# v2_0_-_Calibra_o.net
KiCad netlist of a schematic drawn in EAGLE
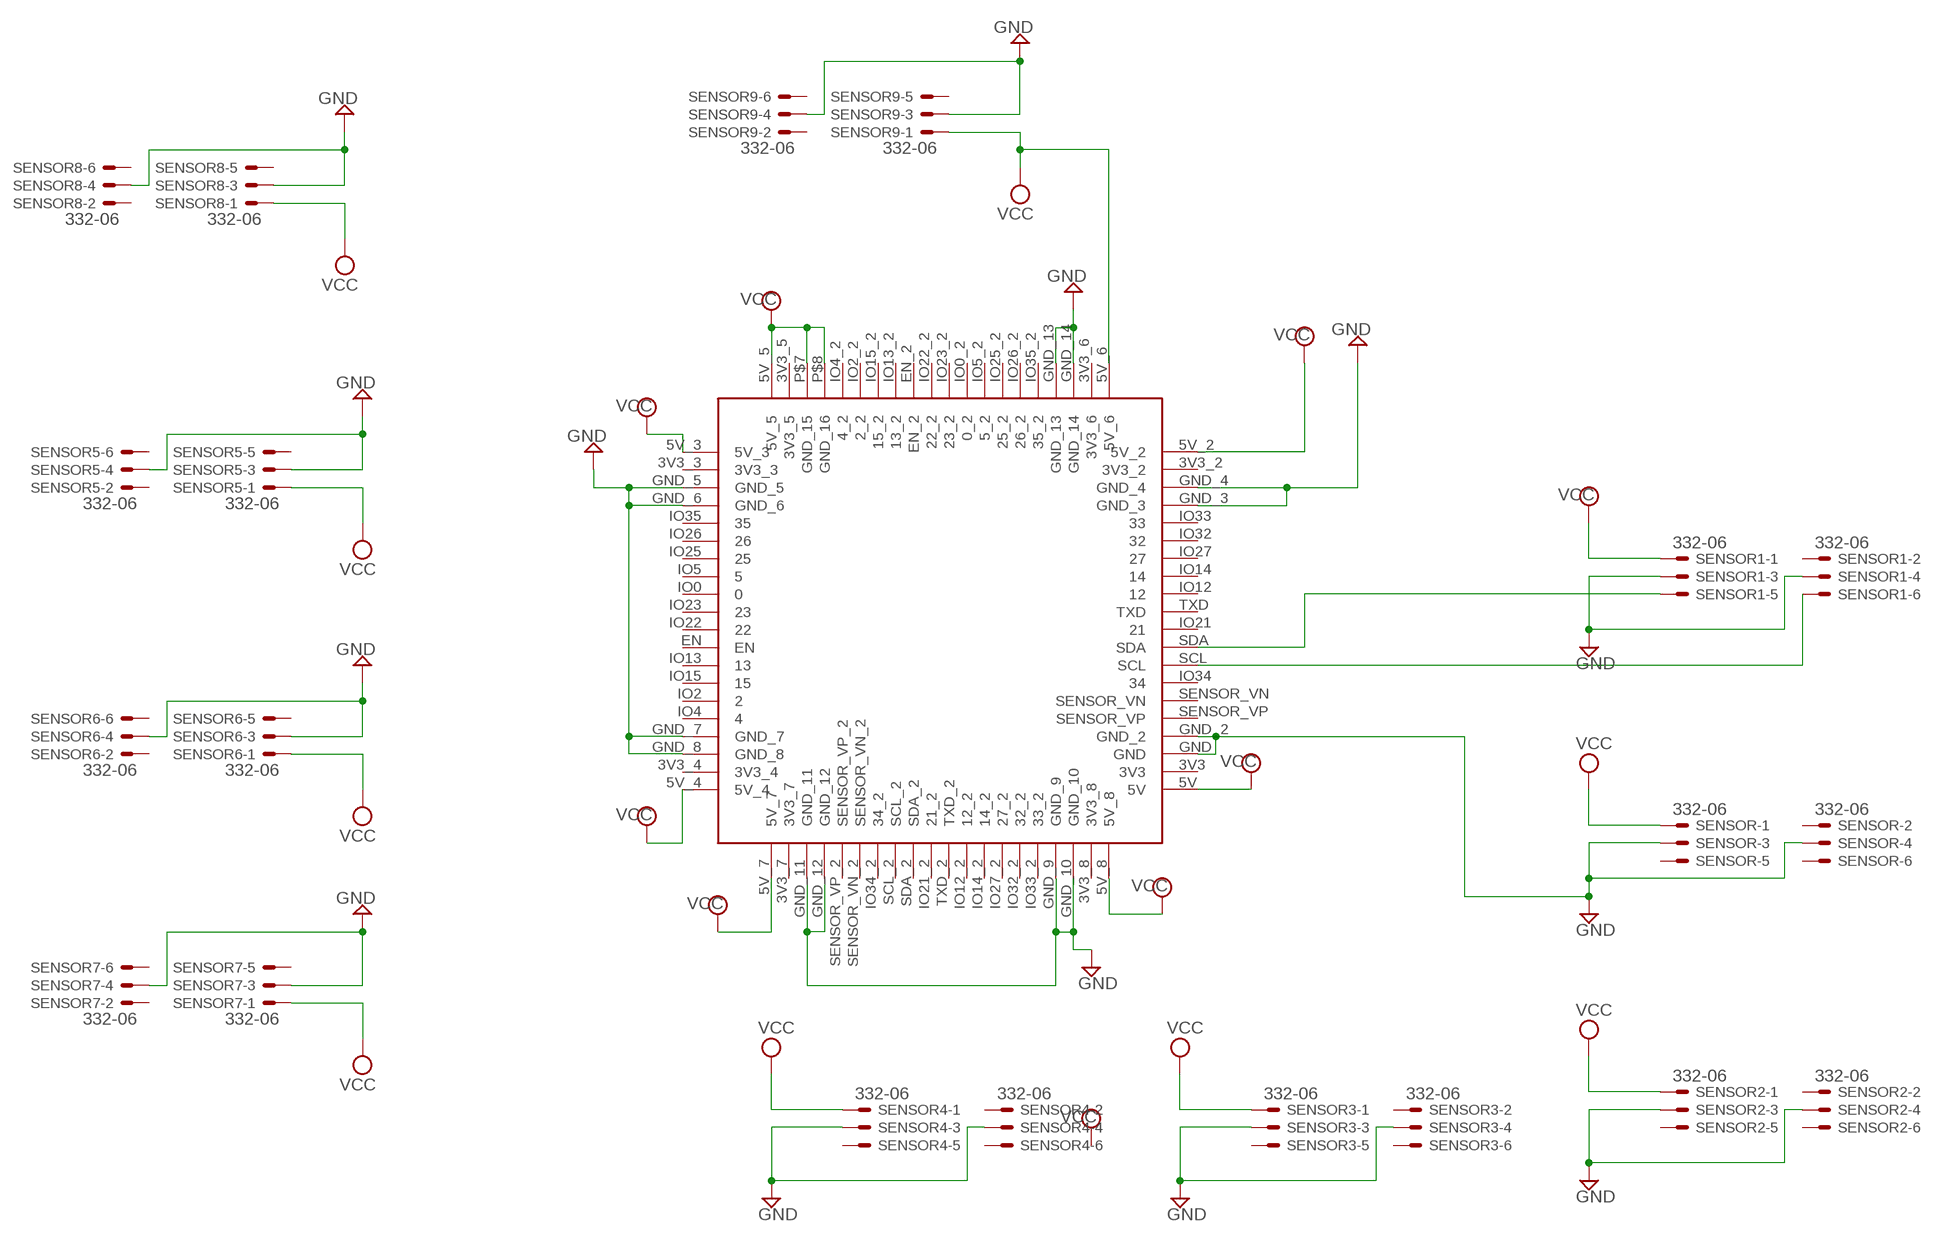
[diagram p0: schematic, sheet 1]

(export (version "E")
  (design (tool "Eeschema 10.0.6"))
  (components
    (comp (ref "SENSOR")
      (value "332-06")
      (footprint "eagle-import:332-06")
      (libsource (lib "eagle-import") (part "332-06"))
    )
    (comp (ref "SENSOR1")
      (value "332-06")
      (footprint "eagle-import:332-06")
      (libsource (lib "eagle-import") (part "332-06"))
    )
    (comp (ref "SENSOR2")
      (value "332-06")
      (footprint "eagle-import:332-06")
      (libsource (lib "eagle-import") (part "332-06"))
    )
    (comp (ref "SENSOR3")
      (value "332-06")
      (footprint "eagle-import:332-06")
      (libsource (lib "eagle-import") (part "332-06"))
    )
    (comp (ref "SENSOR4")
      (value "332-06")
      (footprint "eagle-import:332-06")
      (libsource (lib "eagle-import") (part "332-06"))
    )
    (comp (ref "SENSOR5")
      (value "332-06")
      (footprint "eagle-import:332-06")
      (libsource (lib "eagle-import") (part "332-06"))
    )
    (comp (ref "SENSOR6")
      (value "332-06")
      (footprint "eagle-import:332-06")
      (libsource (lib "eagle-import") (part "332-06"))
    )
    (comp (ref "SENSOR7")
      (value "332-06")
      (footprint "eagle-import:332-06")
      (libsource (lib "eagle-import") (part "332-06"))
    )
    (comp (ref "SENSOR8")
      (value "332-06")
      (footprint "eagle-import:332-06")
      (libsource (lib "eagle-import") (part "332-06"))
    )
    (comp (ref "SENSOR9")
      (value "332-06")
      (footprint "eagle-import:332-06")
      (libsource (lib "eagle-import") (part "332-06"))
    )
    (comp (ref "U$1")
      (value "WT32_SC01")
      (footprint "eagle-import:WT32")
      (libsource (lib "eagle-import") (part "WT32_SC01"))
    )
  )
  (nets
    (net (code "1") (name "GND") (class "Default")
      (node (ref "SENSOR") (pin "3") (pinfunction "S_3") (pintype "passive"))
      (node (ref "SENSOR") (pin "4") (pinfunction "S_4") (pintype "passive"))
      (node (ref "SENSOR1") (pin "3") (pinfunction "S_3") (pintype "passive"))
      (node (ref "SENSOR1") (pin "4") (pinfunction "S_4") (pintype "passive"))
      (node (ref "SENSOR2") (pin "3") (pinfunction "S_3") (pintype "passive"))
      (node (ref "SENSOR2") (pin "4") (pinfunction "S_4") (pintype "passive"))
      (node (ref "SENSOR3") (pin "3") (pinfunction "S_3") (pintype "passive"))
      (node (ref "SENSOR3") (pin "4") (pinfunction "S_4") (pintype "passive"))
      (node (ref "SENSOR4") (pin "3") (pinfunction "S_3") (pintype "passive"))
      (node (ref "SENSOR4") (pin "4") (pinfunction "S_4") (pintype "passive"))
      (node (ref "SENSOR5") (pin "3") (pinfunction "S_3") (pintype "passive"))
      (node (ref "SENSOR5") (pin "4") (pinfunction "S_4") (pintype "passive"))
      (node (ref "SENSOR6") (pin "3") (pinfunction "S_3") (pintype "passive"))
      (node (ref "SENSOR6") (pin "4") (pinfunction "S_4") (pintype "passive"))
      (node (ref "SENSOR7") (pin "3") (pinfunction "S_3") (pintype "passive"))
      (node (ref "SENSOR7") (pin "4") (pinfunction "S_4") (pintype "passive"))
      (node (ref "SENSOR8") (pin "3") (pinfunction "S_3") (pintype "passive"))
      (node (ref "SENSOR8") (pin "4") (pinfunction "S_4") (pintype "passive"))
      (node (ref "SENSOR9") (pin "3") (pinfunction "S_3") (pintype "passive"))
      (node (ref "SENSOR9") (pin "4") (pinfunction "S_4") (pintype "passive"))
      (node (ref "U$1") (pin "GND") (pinfunction "GND_GND") (pintype "bidirectional"))
      (node (ref "U$1") (pin "GND_10") (pinfunction "GND_10_GND_10") (pintype "bidirectional"))
      (node (ref "U$1") (pin "GND_11") (pinfunction "GND_11_GND_11") (pintype "bidirectional"))
      (node (ref "U$1") (pin "GND_12") (pinfunction "GND_12_GND_12") (pintype "bidirectional"))
      (node (ref "U$1") (pin "GND_13") (pinfunction "GND_13_GND_13") (pintype "bidirectional"))
      (node (ref "U$1") (pin "GND_14") (pinfunction "GND_14_GND_14") (pintype "bidirectional"))
      (node (ref "U$1") (pin "GND_2") (pinfunction "GND_2_GND_2") (pintype "bidirectional"))
      (node (ref "U$1") (pin "GND_3") (pinfunction "GND_3_GND_3") (pintype "bidirectional"))
      (node (ref "U$1") (pin "GND_4") (pinfunction "GND_4_GND_4") (pintype "bidirectional"))
      (node (ref "U$1") (pin "GND_5") (pinfunction "GND_5_GND_5") (pintype "bidirectional"))
      (node (ref "U$1") (pin "GND_6") (pinfunction "GND_6_GND_6") (pintype "bidirectional"))
      (node (ref "U$1") (pin "GND_7") (pinfunction "GND_7_GND_7") (pintype "bidirectional"))
      (node (ref "U$1") (pin "GND_8") (pinfunction "GND_8_GND_8") (pintype "bidirectional"))
      (node (ref "U$1") (pin "GND_9") (pinfunction "GND_9_GND_9") (pintype "bidirectional"))
    )
    (net (code "2") (name "Net-(SENSOR1E-S)") (class "Default")
      (node (ref "SENSOR1") (pin "5") (pinfunction "S_5") (pintype "passive"))
      (node (ref "U$1") (pin "SDA") (pinfunction "SDA_SDA") (pintype "bidirectional"))
    )
    (net (code "3") (name "Net-(SENSOR1F-S)") (class "Default")
      (node (ref "SENSOR1") (pin "6") (pinfunction "S_6") (pintype "passive"))
      (node (ref "U$1") (pin "SCL") (pinfunction "SCL_SCL") (pintype "bidirectional"))
    )
    (net (code "4") (name "VCC") (class "Default")
      (node (ref "SENSOR") (pin "1") (pinfunction "S_1") (pintype "passive"))
      (node (ref "SENSOR1") (pin "1") (pinfunction "S_1") (pintype "passive"))
      (node (ref "SENSOR2") (pin "1") (pinfunction "S_1") (pintype "passive"))
      (node (ref "SENSOR3") (pin "1") (pinfunction "S_1") (pintype "passive"))
      (node (ref "SENSOR4") (pin "1") (pinfunction "S_1") (pintype "passive"))
      (node (ref "SENSOR5") (pin "1") (pinfunction "S_1") (pintype "passive"))
      (node (ref "SENSOR6") (pin "1") (pinfunction "S_1") (pintype "passive"))
      (node (ref "SENSOR7") (pin "1") (pinfunction "S_1") (pintype "passive"))
      (node (ref "SENSOR8") (pin "1") (pinfunction "S_1") (pintype "passive"))
      (node (ref "SENSOR9") (pin "1") (pinfunction "S_1") (pintype "passive"))
      (node (ref "U$1") (pin "5V") (pinfunction "5V_5V") (pintype "bidirectional"))
      (node (ref "U$1") (pin "5V_2") (pinfunction "5V_2_5V_2") (pintype "bidirectional"))
      (node (ref "U$1") (pin "5V_3") (pinfunction "5V_3_5V_3") (pintype "bidirectional"))
      (node (ref "U$1") (pin "5V_4") (pinfunction "5V_4_5V_4") (pintype "bidirectional"))
      (node (ref "U$1") (pin "5V_5") (pinfunction "5V_5_5V_5") (pintype "bidirectional"))
      (node (ref "U$1") (pin "5V_6") (pinfunction "5V_6_5V_6") (pintype "bidirectional"))
      (node (ref "U$1") (pin "5V_7") (pinfunction "5V_7_5V_7") (pintype "bidirectional"))
      (node (ref "U$1") (pin "5V_8") (pinfunction "5V_8_5V_8") (pintype "bidirectional"))
      (node (ref "U$1") (pin "P$7") (pinfunction "GND_15_P$7") (pintype "bidirectional"))
      (node (ref "U$1") (pin "P$8") (pinfunction "GND_16_P$8") (pintype "bidirectional"))
    )
    (net (code "5") (name "unconnected-(SENSOR1B-S-Pad2)") (class "Default")
      (node (ref "SENSOR1") (pin "2") (pinfunction "S_2") (pintype "passive"))
    )
    (net (code "6") (name "unconnected-(SENSOR2B-S-Pad2)") (class "Default")
      (node (ref "SENSOR2") (pin "2") (pinfunction "S_2") (pintype "passive"))
    )
    (net (code "7") (name "unconnected-(SENSOR2E-S-Pad5)") (class "Default")
      (node (ref "SENSOR2") (pin "5") (pinfunction "S_5") (pintype "passive"))
    )
    (net (code "8") (name "unconnected-(SENSOR2F-S-Pad6)") (class "Default")
      (node (ref "SENSOR2") (pin "6") (pinfunction "S_6") (pintype "passive"))
    )
    (net (code "9") (name "unconnected-(SENSOR3B-S-Pad2)") (class "Default")
      (node (ref "SENSOR3") (pin "2") (pinfunction "S_2") (pintype "passive"))
    )
    (net (code "10") (name "unconnected-(SENSOR3E-S-Pad5)") (class "Default")
      (node (ref "SENSOR3") (pin "5") (pinfunction "S_5") (pintype "passive"))
    )
    (net (code "11") (name "unconnected-(SENSOR3F-S-Pad6)") (class "Default")
      (node (ref "SENSOR3") (pin "6") (pinfunction "S_6") (pintype "passive"))
    )
    (net (code "12") (name "unconnected-(SENSOR4B-S-Pad2)") (class "Default")
      (node (ref "SENSOR4") (pin "2") (pinfunction "S_2") (pintype "passive"))
    )
    (net (code "13") (name "unconnected-(SENSOR4E-S-Pad5)") (class "Default")
      (node (ref "SENSOR4") (pin "5") (pinfunction "S_5") (pintype "passive"))
    )
    (net (code "14") (name "unconnected-(SENSOR4F-S-Pad6)") (class "Default")
      (node (ref "SENSOR4") (pin "6") (pinfunction "S_6") (pintype "passive"))
    )
    (net (code "15") (name "unconnected-(SENSOR5B-S-Pad2)") (class "Default")
      (node (ref "SENSOR5") (pin "2") (pinfunction "S_2") (pintype "passive"))
    )
    (net (code "16") (name "unconnected-(SENSOR5E-S-Pad5)") (class "Default")
      (node (ref "SENSOR5") (pin "5") (pinfunction "S_5") (pintype "passive"))
    )
    (net (code "17") (name "unconnected-(SENSOR5F-S-Pad6)") (class "Default")
      (node (ref "SENSOR5") (pin "6") (pinfunction "S_6") (pintype "passive"))
    )
    (net (code "18") (name "unconnected-(SENSOR6B-S-Pad2)") (class "Default")
      (node (ref "SENSOR6") (pin "2") (pinfunction "S_2") (pintype "passive"))
    )
    (net (code "19") (name "unconnected-(SENSOR6E-S-Pad5)") (class "Default")
      (node (ref "SENSOR6") (pin "5") (pinfunction "S_5") (pintype "passive"))
    )
    (net (code "20") (name "unconnected-(SENSOR6F-S-Pad6)") (class "Default")
      (node (ref "SENSOR6") (pin "6") (pinfunction "S_6") (pintype "passive"))
    )
    (net (code "21") (name "unconnected-(SENSOR7B-S-Pad2)") (class "Default")
      (node (ref "SENSOR7") (pin "2") (pinfunction "S_2") (pintype "passive"))
    )
    (net (code "22") (name "unconnected-(SENSOR7E-S-Pad5)") (class "Default")
      (node (ref "SENSOR7") (pin "5") (pinfunction "S_5") (pintype "passive"))
    )
    (net (code "23") (name "unconnected-(SENSOR7F-S-Pad6)") (class "Default")
      (node (ref "SENSOR7") (pin "6") (pinfunction "S_6") (pintype "passive"))
    )
    (net (code "24") (name "unconnected-(SENSOR8B-S-Pad2)") (class "Default")
      (node (ref "SENSOR8") (pin "2") (pinfunction "S_2") (pintype "passive"))
    )
    (net (code "25") (name "unconnected-(SENSOR8E-S-Pad5)") (class "Default")
      (node (ref "SENSOR8") (pin "5") (pinfunction "S_5") (pintype "passive"))
    )
    (net (code "26") (name "unconnected-(SENSOR8F-S-Pad6)") (class "Default")
      (node (ref "SENSOR8") (pin "6") (pinfunction "S_6") (pintype "passive"))
    )
    (net (code "27") (name "unconnected-(SENSOR9B-S-Pad2)") (class "Default")
      (node (ref "SENSOR9") (pin "2") (pinfunction "S_2") (pintype "passive"))
    )
    (net (code "28") (name "unconnected-(SENSOR9E-S-Pad5)") (class "Default")
      (node (ref "SENSOR9") (pin "5") (pinfunction "S_5") (pintype "passive"))
    )
    (net (code "29") (name "unconnected-(SENSOR9F-S-Pad6)") (class "Default")
      (node (ref "SENSOR9") (pin "6") (pinfunction "S_6") (pintype "passive"))
    )
    (net (code "30") (name "unconnected-(SENSORB-S-Pad2)") (class "Default")
      (node (ref "SENSOR") (pin "2") (pinfunction "S_2") (pintype "passive"))
    )
    (net (code "31") (name "unconnected-(SENSORE-S-Pad5)") (class "Default")
      (node (ref "SENSOR") (pin "5") (pinfunction "S_5") (pintype "passive"))
    )
    (net (code "32") (name "unconnected-(SENSORF-S-Pad6)") (class "Default")
      (node (ref "SENSOR") (pin "6") (pinfunction "S_6") (pintype "passive"))
    )
    (net (code "33") (name "unconnected-(U$1-0-PadIO0)") (class "Default")
      (node (ref "U$1") (pin "IO0") (pinfunction "0_IO0") (pintype "bidirectional"))
    )
    (net (code "34") (name "unconnected-(U$1-0_2-PadIO0_2)") (class "Default")
      (node (ref "U$1") (pin "IO0_2") (pinfunction "0_2_IO0_2") (pintype "bidirectional"))
    )
    (net (code "35") (name "unconnected-(U$1-2-PadIO2)") (class "Default")
      (node (ref "U$1") (pin "IO2") (pinfunction "2_IO2") (pintype "bidirectional"))
    )
    (net (code "36") (name "unconnected-(U$1-2_2-PadIO2_2)") (class "Default")
      (node (ref "U$1") (pin "IO2_2") (pinfunction "2_2_IO2_2") (pintype "bidirectional"))
    )
    (net (code "37") (name "unconnected-(U$1-4-PadIO4)") (class "Default")
      (node (ref "U$1") (pin "IO4") (pinfunction "4_IO4") (pintype "bidirectional"))
    )
    (net (code "38") (name "unconnected-(U$1-4_2-PadIO4_2)") (class "Default")
      (node (ref "U$1") (pin "IO4_2") (pinfunction "4_2_IO4_2") (pintype "bidirectional"))
    )
    (net (code "39") (name "unconnected-(U$1-5-PadIO5)") (class "Default")
      (node (ref "U$1") (pin "IO5") (pinfunction "5_IO5") (pintype "bidirectional"))
    )
    (net (code "40") (name "unconnected-(U$1-5_2-PadIO5_2)") (class "Default")
      (node (ref "U$1") (pin "IO5_2") (pinfunction "5_2_IO5_2") (pintype "bidirectional"))
    )
    (net (code "41") (name "unconnected-(U$1-12-PadIO12)") (class "Default")
      (node (ref "U$1") (pin "IO12") (pinfunction "12_IO12") (pintype "bidirectional"))
    )
    (net (code "42") (name "unconnected-(U$1-12_2-PadIO12_2)") (class "Default")
      (node (ref "U$1") (pin "IO12_2") (pinfunction "12_2_IO12_2") (pintype "bidirectional"))
    )
    (net (code "43") (name "unconnected-(U$1-13-PadIO13)") (class "Default")
      (node (ref "U$1") (pin "IO13") (pinfunction "13_IO13") (pintype "bidirectional"))
    )
    (net (code "44") (name "unconnected-(U$1-13_2-PadIO13_2)") (class "Default")
      (node (ref "U$1") (pin "IO13_2") (pinfunction "13_2_IO13_2") (pintype "bidirectional"))
    )
    (net (code "45") (name "unconnected-(U$1-14-PadIO14)") (class "Default")
      (node (ref "U$1") (pin "IO14") (pinfunction "14_IO14") (pintype "bidirectional"))
    )
    (net (code "46") (name "unconnected-(U$1-14_2-PadIO14_2)") (class "Default")
      (node (ref "U$1") (pin "IO14_2") (pinfunction "14_2_IO14_2") (pintype "bidirectional"))
    )
    (net (code "47") (name "unconnected-(U$1-15-PadIO15)") (class "Default")
      (node (ref "U$1") (pin "IO15") (pinfunction "15_IO15") (pintype "bidirectional"))
    )
    (net (code "48") (name "unconnected-(U$1-15_2-PadIO15_2)") (class "Default")
      (node (ref "U$1") (pin "IO15_2") (pinfunction "15_2_IO15_2") (pintype "bidirectional"))
    )
    (net (code "49") (name "unconnected-(U$1-21-PadIO21)") (class "Default")
      (node (ref "U$1") (pin "IO21") (pinfunction "21_IO21") (pintype "bidirectional"))
    )
    (net (code "50") (name "unconnected-(U$1-21_2-PadIO21_2)") (class "Default")
      (node (ref "U$1") (pin "IO21_2") (pinfunction "21_2_IO21_2") (pintype "bidirectional"))
    )
    (net (code "51") (name "unconnected-(U$1-22-PadIO22)") (class "Default")
      (node (ref "U$1") (pin "IO22") (pinfunction "22_IO22") (pintype "bidirectional"))
    )
    (net (code "52") (name "unconnected-(U$1-22_2-PadIO22_2)") (class "Default")
      (node (ref "U$1") (pin "IO22_2") (pinfunction "22_2_IO22_2") (pintype "bidirectional"))
    )
    (net (code "53") (name "unconnected-(U$1-23-PadIO23)") (class "Default")
      (node (ref "U$1") (pin "IO23") (pinfunction "23_IO23") (pintype "bidirectional"))
    )
    (net (code "54") (name "unconnected-(U$1-23_2-PadIO23_2)") (class "Default")
      (node (ref "U$1") (pin "IO23_2") (pinfunction "23_2_IO23_2") (pintype "bidirectional"))
    )
    (net (code "55") (name "unconnected-(U$1-25-PadIO25)") (class "Default")
      (node (ref "U$1") (pin "IO25") (pinfunction "25_IO25") (pintype "bidirectional"))
    )
    (net (code "56") (name "unconnected-(U$1-25_2-PadIO25_2)") (class "Default")
      (node (ref "U$1") (pin "IO25_2") (pinfunction "25_2_IO25_2") (pintype "bidirectional"))
    )
    (net (code "57") (name "unconnected-(U$1-26-PadIO26)") (class "Default")
      (node (ref "U$1") (pin "IO26") (pinfunction "26_IO26") (pintype "bidirectional"))
    )
    (net (code "58") (name "unconnected-(U$1-26_2-PadIO26_2)") (class "Default")
      (node (ref "U$1") (pin "IO26_2") (pinfunction "26_2_IO26_2") (pintype "bidirectional"))
    )
    (net (code "59") (name "unconnected-(U$1-27-PadIO27)") (class "Default")
      (node (ref "U$1") (pin "IO27") (pinfunction "27_IO27") (pintype "bidirectional"))
    )
    (net (code "60") (name "unconnected-(U$1-27_2-PadIO27_2)") (class "Default")
      (node (ref "U$1") (pin "IO27_2") (pinfunction "27_2_IO27_2") (pintype "bidirectional"))
    )
    (net (code "61") (name "unconnected-(U$1-32-PadIO32)") (class "Default")
      (node (ref "U$1") (pin "IO32") (pinfunction "32_IO32") (pintype "bidirectional"))
    )
    (net (code "62") (name "unconnected-(U$1-32_2-PadIO32_2)") (class "Default")
      (node (ref "U$1") (pin "IO32_2") (pinfunction "32_2_IO32_2") (pintype "bidirectional"))
    )
    (net (code "63") (name "unconnected-(U$1-33-PadIO33)") (class "Default")
      (node (ref "U$1") (pin "IO33") (pinfunction "33_IO33") (pintype "bidirectional"))
    )
    (net (code "64") (name "unconnected-(U$1-33_2-PadIO33_2)") (class "Default")
      (node (ref "U$1") (pin "IO33_2") (pinfunction "33_2_IO33_2") (pintype "bidirectional"))
    )
    (net (code "65") (name "unconnected-(U$1-34-PadIO34)") (class "Default")
      (node (ref "U$1") (pin "IO34") (pinfunction "34_IO34") (pintype "bidirectional"))
    )
    (net (code "66") (name "unconnected-(U$1-34_2-PadIO34_2)") (class "Default")
      (node (ref "U$1") (pin "IO34_2") (pinfunction "34_2_IO34_2") (pintype "bidirectional"))
    )
    (net (code "67") (name "unconnected-(U$1-35-PadIO35)") (class "Default")
      (node (ref "U$1") (pin "IO35") (pinfunction "35_IO35") (pintype "bidirectional"))
    )
    (net (code "68") (name "unconnected-(U$1-35_2-PadIO35_2)") (class "Default")
      (node (ref "U$1") (pin "IO35_2") (pinfunction "35_2_IO35_2") (pintype "bidirectional"))
    )
    (net (code "69") (name "unconnected-(U$1-Pad3V3)") (class "Default")
      (node (ref "U$1") (pin "3V3") (pinfunction "3V3_3V3") (pintype "bidirectional"))
    )
    (net (code "70") (name "unconnected-(U$1-Pad3V3_2)") (class "Default")
      (node (ref "U$1") (pin "3V3_2") (pinfunction "3V3_2_3V3_2") (pintype "bidirectional"))
    )
    (net (code "71") (name "unconnected-(U$1-Pad3V3_3)") (class "Default")
      (node (ref "U$1") (pin "3V3_3") (pinfunction "3V3_3_3V3_3") (pintype "bidirectional"))
    )
    (net (code "72") (name "unconnected-(U$1-Pad3V3_4)") (class "Default")
      (node (ref "U$1") (pin "3V3_4") (pinfunction "3V3_4_3V3_4") (pintype "bidirectional"))
    )
    (net (code "73") (name "unconnected-(U$1-Pad3V3_5)") (class "Default")
      (node (ref "U$1") (pin "3V3_5") (pinfunction "3V3_5_3V3_5") (pintype "bidirectional"))
    )
    (net (code "74") (name "unconnected-(U$1-Pad3V3_6)") (class "Default")
      (node (ref "U$1") (pin "3V3_6") (pinfunction "3V3_6_3V3_6") (pintype "bidirectional"))
    )
    (net (code "75") (name "unconnected-(U$1-Pad3V3_7)") (class "Default")
      (node (ref "U$1") (pin "3V3_7") (pinfunction "3V3_7_3V3_7") (pintype "bidirectional"))
    )
    (net (code "76") (name "unconnected-(U$1-Pad3V3_8)") (class "Default")
      (node (ref "U$1") (pin "3V3_8") (pinfunction "3V3_8_3V3_8") (pintype "bidirectional"))
    )
    (net (code "77") (name "unconnected-(U$1-PadEN)") (class "Default")
      (node (ref "U$1") (pin "EN") (pinfunction "EN_EN") (pintype "bidirectional"))
    )
    (net (code "78") (name "unconnected-(U$1-PadEN_2)") (class "Default")
      (node (ref "U$1") (pin "EN_2") (pinfunction "EN_2_EN_2") (pintype "bidirectional"))
    )
    (net (code "79") (name "unconnected-(U$1-PadSCL_2)") (class "Default")
      (node (ref "U$1") (pin "SCL_2") (pinfunction "SCL_2_SCL_2") (pintype "bidirectional"))
    )
    (net (code "80") (name "unconnected-(U$1-PadSDA_2)") (class "Default")
      (node (ref "U$1") (pin "SDA_2") (pinfunction "SDA_2_SDA_2") (pintype "bidirectional"))
    )
    (net (code "81") (name "unconnected-(U$1-PadSENSOR_VN)") (class "Default")
      (node (ref "U$1") (pin "SENSOR_VN") (pinfunction "SENSOR_VN_SENSOR_VN") (pintype "bidirectional"))
    )
    (net (code "82") (name "unconnected-(U$1-PadSENSOR_VN_2)") (class "Default")
      (node (ref "U$1") (pin "SENSOR_VN_2") (pinfunction "SENSOR_VN_2_SENSOR_VN_2") (pintype "bidirectional"))
    )
    (net (code "83") (name "unconnected-(U$1-PadSENSOR_VP)") (class "Default")
      (node (ref "U$1") (pin "SENSOR_VP") (pinfunction "SENSOR_VP_SENSOR_VP") (pintype "bidirectional"))
    )
    (net (code "84") (name "unconnected-(U$1-PadSENSOR_VP_2)") (class "Default")
      (node (ref "U$1") (pin "SENSOR_VP_2") (pinfunction "SENSOR_VP_2_SENSOR_VP_2") (pintype "bidirectional"))
    )
    (net (code "85") (name "unconnected-(U$1-PadTXD)") (class "Default")
      (node (ref "U$1") (pin "TXD") (pinfunction "TXD_TXD") (pintype "bidirectional"))
    )
    (net (code "86") (name "unconnected-(U$1-PadTXD_2)") (class "Default")
      (node (ref "U$1") (pin "TXD_2") (pinfunction "TXD_2_TXD_2") (pintype "bidirectional"))
    )
  )
)
